# TRV1_0.net
KiCad netlist of a schematic drawn in Altium Designer
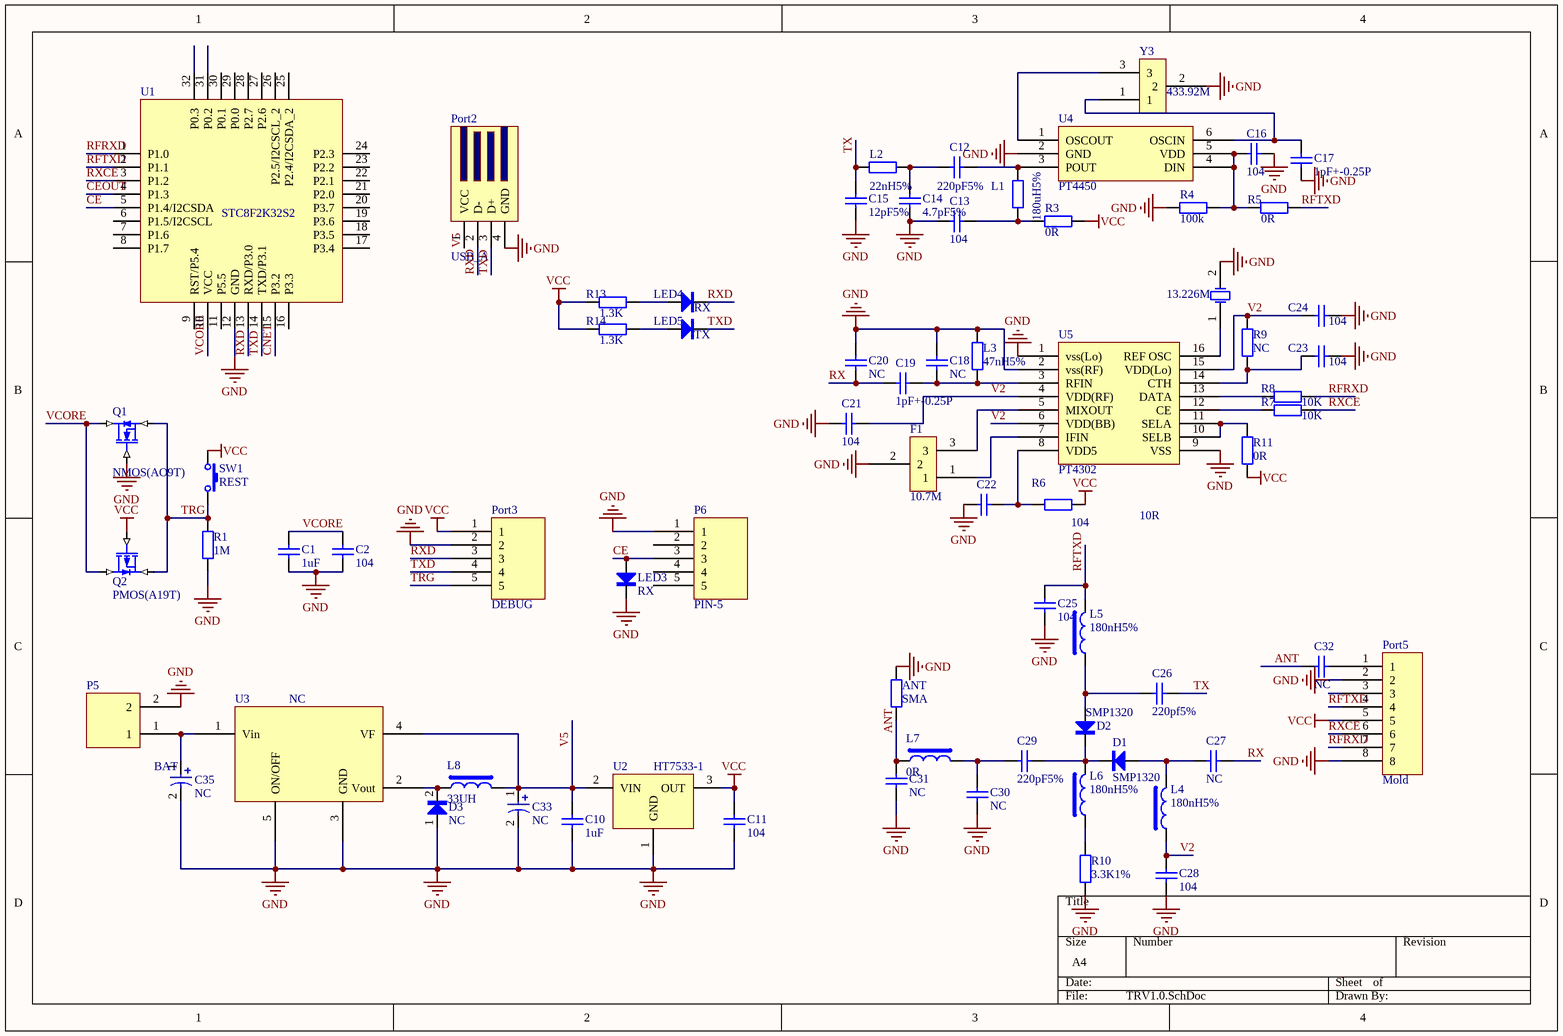
[diagram p0: TRV1.0.SchDoc]

(export (version "E")
  (design (tool "Eeschema 10.0.6"))
  (components
    (comp (ref "ANT")
      (value "SMA")
      (footprint "SWA-KE天线母座")
      (description "Resistor")
      (fields (field (name "PUBLISHER") "Altium Limited"))
      (libsource (lib "") (part "Res2_2"))
    )
    (comp (ref "C1")
      (value "1uF")
      (footprint "0603")
      (description "Capacitor")
      (fields (field (name "PUBLISHER") "Altium Limited"))
      (libsource (lib "Miscellaneous Devices") (part "Cap"))
    )
    (comp (ref "C2")
      (value "104")
      (footprint "0603")
      (description "Capacitor")
      (fields (field (name "PUBLISHER") "Altium Limited"))
      (libsource (lib "Miscellaneous Devices") (part "Cap"))
    )
    (comp (ref "C10")
      (value "1uF")
      (footprint "0603")
      (description "Capacitor")
      (fields (field (name "PUBLISHER") "Altium Limited"))
      (libsource (lib "Miscellaneous Devices") (part "Cap"))
    )
    (comp (ref "C11")
      (value "104")
      (footprint "0603")
      (description "Capacitor")
      (fields (field (name "PUBLISHER") "Altium Limited"))
      (libsource (lib "Miscellaneous Devices") (part "Cap"))
    )
    (comp (ref "C12")
      (value "220pF5%")
      (footprint "0603")
      (description "Capacitor")
      (fields (field (name "PUBLISHER") "Altium Limited"))
      (libsource (lib "Miscellaneous Devices") (part "Cap"))
    )
    (comp (ref "C13")
      (value "104")
      (footprint "0603")
      (description "Capacitor")
      (fields (field (name "PUBLISHER") "Altium Limited"))
      (libsource (lib "Miscellaneous Devices") (part "Cap"))
    )
    (comp (ref "C14")
      (value "4.7pF5%")
      (footprint "0603")
      (description "Capacitor")
      (fields (field (name "PUBLISHER") "Altium Limited"))
      (libsource (lib "Miscellaneous Devices") (part "Cap"))
    )
    (comp (ref "C15")
      (value "12pF5%")
      (footprint "0603")
      (description "Capacitor")
      (fields (field (name "PUBLISHER") "Altium Limited"))
      (libsource (lib "Miscellaneous Devices") (part "Cap"))
    )
    (comp (ref "C16")
      (value "104")
      (footprint "0603")
      (description "Capacitor")
      (fields (field (name "PUBLISHER") "Altium Limited"))
      (libsource (lib "Miscellaneous Devices") (part "Cap"))
    )
    (comp (ref "C17")
      (value "1pF+-0.25P")
      (footprint "0603")
      (description "Capacitor")
      (fields (field (name "PUBLISHER") "Altium Limited"))
      (libsource (lib "Miscellaneous Devices") (part "Cap"))
    )
    (comp (ref "C18")
      (value "NC")
      (footprint "0603")
      (description "Capacitor")
      (fields (field (name "PUBLISHER") "Altium Limited"))
      (libsource (lib "Miscellaneous Devices") (part "Cap"))
    )
    (comp (ref "C19")
      (value "1pF+-0.25P")
      (footprint "0603")
      (description "Capacitor")
      (fields (field (name "PUBLISHER") "Altium Limited"))
      (libsource (lib "Miscellaneous Devices") (part "Cap"))
    )
    (comp (ref "C20")
      (value "NC")
      (footprint "0603")
      (description "Capacitor")
      (fields (field (name "PUBLISHER") "Altium Limited"))
      (libsource (lib "Miscellaneous Devices") (part "Cap"))
    )
    (comp (ref "C21")
      (value "104")
      (footprint "0603")
      (description "Capacitor")
      (fields (field (name "PUBLISHER") "Altium Limited"))
      (libsource (lib "Miscellaneous Devices") (part "Cap"))
    )
    (comp (ref "C22")
      (value "104")
      (footprint "0603")
      (description "Capacitor")
      (fields (field (name "PUBLISHER") "Altium Limited"))
      (libsource (lib "Miscellaneous Devices") (part "Cap"))
    )
    (comp (ref "C23")
      (value "104")
      (footprint "0603")
      (description "Capacitor")
      (fields (field (name "PUBLISHER") "Altium Limited"))
      (libsource (lib "Miscellaneous Devices") (part "Cap"))
    )
    (comp (ref "C24")
      (value "104")
      (footprint "0603")
      (description "Capacitor")
      (fields (field (name "PUBLISHER") "Altium Limited"))
      (libsource (lib "Miscellaneous Devices") (part "Cap"))
    )
    (comp (ref "C25")
      (value "104")
      (footprint "0603")
      (description "Capacitor")
      (fields (field (name "PUBLISHER") "Altium Limited"))
      (libsource (lib "Miscellaneous Devices") (part "Cap"))
    )
    (comp (ref "C26")
      (value "220pf5%")
      (footprint "0603")
      (description "Capacitor")
      (fields (field (name "PUBLISHER") "Altium Limited"))
      (libsource (lib "Miscellaneous Devices") (part "Cap"))
    )
    (comp (ref "C27")
      (value "NC")
      (footprint "0603")
      (description "Capacitor")
      (fields (field (name "PUBLISHER") "Altium Limited"))
      (libsource (lib "Miscellaneous Devices") (part "Cap"))
    )
    (comp (ref "C28")
      (value "104")
      (footprint "0603")
      (description "Capacitor")
      (fields (field (name "PUBLISHER") "Altium Limited"))
      (libsource (lib "Miscellaneous Devices") (part "Cap"))
    )
    (comp (ref "C29")
      (value "220pF5%")
      (footprint "0603")
      (description "Capacitor")
      (fields (field (name "PUBLISHER") "Altium Limited"))
      (libsource (lib "Miscellaneous Devices") (part "Cap"))
    )
    (comp (ref "C30")
      (value "NC")
      (footprint "0603")
      (description "Capacitor")
      (fields (field (name "PUBLISHER") "Altium Limited"))
      (libsource (lib "Miscellaneous Devices") (part "Cap"))
    )
    (comp (ref "C31")
      (value "NC")
      (footprint "0603")
      (description "Capacitor")
      (fields (field (name "PUBLISHER") "Altium Limited"))
      (libsource (lib "Miscellaneous Devices") (part "Cap"))
    )
    (comp (ref "C32")
      (value "NC")
      (footprint "0603")
      (description "Capacitor")
      (fields (field (name "PUBLISHER") "Altium Limited"))
      (libsource (lib "Miscellaneous Devices") (part "Cap"))
    )
    (comp (ref "C33") (value "NC") (footprint "CAP6*12") (libsource (lib "dajiang SCH -DXP") (part "CAP2")))
    (comp (ref "C35") (value "NC") (footprint "CAP6*12") (libsource (lib "dajiang SCH -DXP") (part "CAP2")))
    (comp (ref "D1")
      (value "SMP1320")
      (footprint "0603")
      (description "diode")
      (libsource (lib "") (part "DIODE_2"))
    )
    (comp (ref "D2")
      (value "SMP1320")
      (footprint "0603")
      (description "diode")
      (libsource (lib "") (part "DIODE_1"))
    )
    (comp (ref "D3")
      (value "NC")
      (footprint "SS34")
      (description "diode")
      (libsource (lib "dajiang SCH -DXP") (part "DIODE"))
    )
    (comp (ref "F1") (value "10.7M") (footprint "PT4450 XTAL") (libsource (lib "MYSHC") (part "Filter")))
    (comp (ref "L1")
      (value "180uH5%")
      (footprint "0603")
      (description "Resistor")
      (fields (field (name "PUBLISHER") "Altium Limited"))
      (libsource (lib "") (part "Res2_1"))
    )
    (comp (ref "L2")
      (value "22nH5%")
      (footprint "0603")
      (description "Resistor")
      (fields (field (name "PUBLISHER") "Altium Limited"))
      (libsource (lib "") (part "Res2_3"))
    )
    (comp (ref "L3")
      (value "47nH5%")
      (footprint "0603")
      (description "Resistor")
      (fields (field (name "PUBLISHER") "Altium Limited"))
      (libsource (lib "") (part "Res2_2"))
    )
    (comp (ref "L4")
      (value "180nH5%")
      (footprint "0603")
      (description "Inductor")
      (libsource (lib "dajiang SCH -DXP") (part "L"))
    )
    (comp (ref "L5")
      (value "180nH5%")
      (footprint "0603")
      (description "Inductor")
      (libsource (lib "dajiang SCH -DXP") (part "L"))
    )
    (comp (ref "L6")
      (value "180nH5%")
      (footprint "0603")
      (description "Inductor")
      (libsource (lib "dajiang SCH -DXP") (part "L"))
    )
    (comp (ref "L7")
      (value "0R")
      (footprint "0603")
      (description "Inductor")
      (libsource (lib "") (part "L_1"))
    )
    (comp (ref "L8")
      (value "33UH")
      (footprint "CD75")
      (description "Inductor")
      (libsource (lib "") (part "L_1"))
    )
    (comp (ref "LED3")
      (value "RX")
      (footprint "LED-0603")
      (description "diode")
      (libsource (lib "") (part "DIODE_1"))
    )
    (comp (ref "LED4")
      (value "RX")
      (footprint "LED-0603")
      (description "diode")
      (libsource (lib "") (part "DIODE_3"))
    )
    (comp (ref "LED5")
      (value "TX")
      (footprint "LED-0603")
      (description "diode")
      (libsource (lib "") (part "DIODE_3"))
    )
    (comp (ref "P5") (value "BAT") (footprint "DIP2-2.54") (libsource (lib "MYSHC") (part "BAT")))
    (comp (ref "P6") (value "PIN-5") (footprint "PCBComponent_1") (libsource (lib "MYSHC") (part "PIN-5")))
    (comp (ref "Port2") (value "USB_A") (footprint "USB-A") (libsource (lib "mylib") (part "USB")))
    (comp (ref "Port3") (value "DEBUG") (footprint "STC_DEBUG") (libsource (lib "MYSHC") (part "PIN-5")))
    (comp (ref "Port5") (value "Mold") (footprint "Pin-8") (libsource (lib "MYSHC") (part "Pin-8")))
    (comp (ref "Q1")
      (value "NMOS(AO9T)")
      (footprint "SOT-23")
      (description "mosfet")
      (libsource (lib "dajiang SCH -DXP") (part "MOSFET-N"))
    )
    (comp (ref "Q2")
      (value "PMOS(A19T)")
      (footprint "SOT-23")
      (description "mosfet")
      (libsource (lib "dajiang SCH -DXP") (part "MOSFET-P"))
    )
    (comp (ref "R1")
      (value "1M")
      (footprint "0603")
      (description "Resistor")
      (fields (field (name "PUBLISHER") "Altium Limited"))
      (libsource (lib "") (part "Res2_2"))
    )
    (comp (ref "R3")
      (value "0R")
      (footprint "0603")
      (description "Resistor")
      (fields (field (name "PUBLISHER") "Altium Limited"))
      (libsource (lib "Miscellaneous Devices") (part "Res2"))
    )
    (comp (ref "R4")
      (value "100k")
      (footprint "0603")
      (description "Resistor")
      (fields (field (name "PUBLISHER") "Altium Limited"))
      (libsource (lib "Miscellaneous Devices") (part "Res2"))
    )
    (comp (ref "R5")
      (value "0R")
      (footprint "0603")
      (description "Resistor")
      (fields (field (name "PUBLISHER") "Altium Limited"))
      (libsource (lib "Miscellaneous Devices") (part "Res2"))
    )
    (comp (ref "R6")
      (value "10R")
      (footprint "0603")
      (description "Resistor")
      (fields (field (name "PUBLISHER") "Altium Limited"))
      (libsource (lib "Miscellaneous Devices") (part "Res2"))
    )
    (comp (ref "R7")
      (value "10K")
      (footprint "0603")
      (description "Resistor")
      (fields (field (name "PUBLISHER") "Altium Limited"))
      (libsource (lib "Miscellaneous Devices") (part "Res2"))
    )
    (comp (ref "R8")
      (value "10K")
      (footprint "0603")
      (description "Resistor")
      (fields (field (name "PUBLISHER") "Altium Limited"))
      (libsource (lib "Miscellaneous Devices") (part "Res2"))
    )
    (comp (ref "R9")
      (value "NC")
      (footprint "0603")
      (description "Resistor")
      (fields (field (name "PUBLISHER") "Altium Limited"))
      (libsource (lib "") (part "Res2_1"))
    )
    (comp (ref "R10")
      (value "3.3K1%")
      (footprint "0603")
      (description "Resistor")
      (fields (field (name "PUBLISHER") "Altium Limited"))
      (libsource (lib "") (part "Res2_1"))
    )
    (comp (ref "R11")
      (value "0R")
      (footprint "0603")
      (description "Resistor")
      (fields (field (name "PUBLISHER") "Altium Limited"))
      (libsource (lib "") (part "Res2_1"))
    )
    (comp (ref "R13")
      (value "1.3K")
      (footprint "0603")
      (description "Resistor")
      (fields (field (name "PUBLISHER") "Altium Limited"))
      (libsource (lib "Miscellaneous Devices") (part "Res2"))
    )
    (comp (ref "R14")
      (value "1.3K")
      (footprint "0603")
      (description "Resistor")
      (fields (field (name "PUBLISHER") "Altium Limited"))
      (libsource (lib "Miscellaneous Devices") (part "Res2"))
    )
    (comp (ref "SW1")
      (value "REST")
      (footprint "SW-1")
      (description "key")
      (libsource (lib "dajiang SCH -DXP") (part "SW-P"))
    )
    (comp (ref "U1")
      (value "STC8F2K32S2")
      (footprint "LQPF-32")
      (libsource (lib "mylib") (part "STC8F2K64S2"))
    )
    (comp (ref "U2") (value "HT7533-1") (footprint "3A5A3D") (libsource (lib "mylib") (part "HT7533-1")))
    (comp (ref "U3") (value "NC") (footprint "TS5B_N") (libsource (lib "MYSHC") (part "LM2596")))
    (comp (ref "U4") (value "PT4450") (libsource (lib "MYSHC") (part "PT4450")))
    (comp (ref "U5") (value "PT4302") (footprint "PT4302") (libsource (lib "MYSHC") (part "PT4302")))
    (comp (ref "Y3")
      (value "433.92M")
      (footprint "PT4450 XTAL")
      (libsource (lib "MYSHC") (part "PT4450-XTAL"))
    )
    (comp (ref "Y4")
      (value "13.226M")
      (footprint "PT4306 XTAL")
      (description "Crystal Oscillator")
      (libsource (lib "DT-852A(3)") (part "XTAL"))
    )
  )
  (nets
    (net (code "1") (name "/ANT") (class "Default")
      (node (ref "ANT") (pin "1") (pinfunction "1_1") (pintype "passive"))
      (node (ref "C31") (pin "1") (pinfunction "1_1") (pintype "passive"))
      (node (ref "C32") (pin "1") (pinfunction "1_1") (pintype "passive"))
      (node (ref "L7") (pin "1") (pinfunction "1_1") (pintype "passive"))
    )
    (net (code "2") (name "/CE") (class "Default")
      (node (ref "LED3") (pin "1") (pinfunction "1_1") (pintype "passive"))
      (node (ref "P6") (pin "3") (pinfunction "3_3") (pintype "passive"))
      (node (ref "U1") (pin "5") (pinfunction "P1.4/I2CSDA_5") (pintype "passive"))
    )
    (net (code "3") (name "/CEOUT") (class "Default")
      (node (ref "U1") (pin "4") (pinfunction "P1.3_4") (pintype "passive"))
    )
    (net (code "4") (name "/CNET") (class "Default")
      (node (ref "U1") (pin "15") (pinfunction "P3.2_15") (pintype "passive"))
    )
    (net (code "5") (name "/RFRXD") (class "Default")
      (node (ref "Port5") (pin "7") (pinfunction "7_7") (pintype "passive"))
      (node (ref "R8") (pin "1") (pinfunction "1_1") (pintype "passive"))
      (node (ref "U1") (pin "1") (pinfunction "P1.0_1") (pintype "passive"))
    )
    (net (code "6") (name "/RFTXD") (class "Default")
      (node (ref "C25") (pin "1") (pinfunction "1_1") (pintype "passive"))
      (node (ref "L5") (pin "2") (pinfunction "2_2") (pintype "passive"))
      (node (ref "Port5") (pin "4") (pinfunction "4_4") (pintype "passive"))
      (node (ref "R5") (pin "1") (pinfunction "1_1") (pintype "passive"))
      (node (ref "U1") (pin "2") (pinfunction "P1.1_2") (pintype "passive"))
    )
    (net (code "7") (name "/RX") (class "Default")
      (node (ref "C19") (pin "1") (pinfunction "1_1") (pintype "passive"))
      (node (ref "C20") (pin "1") (pinfunction "1_1") (pintype "passive"))
      (node (ref "C27") (pin "2") (pinfunction "2_2") (pintype "passive"))
    )
    (net (code "8") (name "/RXCE") (class "Default")
      (node (ref "Port5") (pin "6") (pinfunction "6_6") (pintype "passive"))
      (node (ref "R7") (pin "1") (pinfunction "1_1") (pintype "passive"))
      (node (ref "U1") (pin "3") (pinfunction "P1.2_3") (pintype "passive"))
    )
    (net (code "9") (name "/RXD") (class "Default")
      (node (ref "LED4") (pin "2") (pinfunction "2_2") (pintype "passive"))
      (node (ref "Port2") (pin "2") (pinfunction "D-_2") (pintype "passive"))
      (node (ref "Port3") (pin "3") (pinfunction "3_3") (pintype "passive"))
      (node (ref "U1") (pin "13") (pinfunction "RXD/P3.0_13") (pintype "passive"))
    )
    (net (code "10") (name "/TRG") (class "Default")
      (node (ref "Port3") (pin "5") (pinfunction "5_5") (pintype "passive"))
      (node (ref "Q1") (pin "2") (pinfunction "D_2") (pintype "input"))
      (node (ref "Q2") (pin "2") (pinfunction "S_2") (pintype "input"))
      (node (ref "R1") (pin "2") (pinfunction "2_2") (pintype "passive"))
      (node (ref "SW1") (pin "2") (pinfunction "2_2") (pintype "passive"))
    )
    (net (code "11") (name "/TX") (class "Default")
      (node (ref "C15") (pin "2") (pinfunction "2_2") (pintype "passive"))
      (node (ref "C26") (pin "2") (pinfunction "2_2") (pintype "passive"))
      (node (ref "L2") (pin "1") (pinfunction "1_1") (pintype "passive"))
    )
    (net (code "12") (name "/TXD") (class "Default")
      (node (ref "LED5") (pin "2") (pinfunction "2_2") (pintype "passive"))
      (node (ref "Port2") (pin "3") (pinfunction "D+_3") (pintype "passive"))
      (node (ref "Port3") (pin "4") (pinfunction "4_4") (pintype "passive"))
      (node (ref "U1") (pin "14") (pinfunction "TXD/P3.1_14") (pintype "passive"))
    )
    (net (code "13") (name "/V2") (class "Default")
      (node (ref "C21") (pin "1") (pinfunction "1_1") (pintype "passive"))
      (node (ref "C24") (pin "2") (pinfunction "2_2") (pintype "passive"))
      (node (ref "C28") (pin "2") (pinfunction "2_2") (pintype "passive"))
      (node (ref "L4") (pin "1") (pinfunction "1_1") (pintype "passive"))
      (node (ref "R9") (pin "1") (pinfunction "1_1") (pintype "passive"))
      (node (ref "U5") (pin "15") (pinfunction "VDD(Lo)_15") (pintype "passive"))
      (node (ref "U5") (pin "4") (pinfunction "VDD(RF)_4") (pintype "passive"))
      (node (ref "U5") (pin "6") (pinfunction "VDD(BB)_6") (pintype "passive"))
    )
    (net (code "14") (name "/V5") (class "Default")
      (node (ref "C10") (pin "1") (pinfunction "1_1") (pintype "passive"))
      (node (ref "C33") (pin "1") (pinfunction "1_1") (pintype "passive"))
      (node (ref "L8") (pin "2") (pinfunction "2_2") (pintype "passive"))
      (node (ref "Port2") (pin "1") (pinfunction "VCC_1") (pintype "passive"))
      (node (ref "U2") (pin "2") (pinfunction "VIN_2") (pintype "passive"))
      (node (ref "U3") (pin "4") (pinfunction "VF_4") (pintype "passive"))
    )
    (net (code "15") (name "/VCORE") (class "Default")
      (node (ref "C1") (pin "2") (pinfunction "2_2") (pintype "passive"))
      (node (ref "C2") (pin "2") (pinfunction "2_2") (pintype "passive"))
      (node (ref "Q1") (pin "3") (pinfunction "S_3") (pintype "input"))
      (node (ref "Q2") (pin "3") (pinfunction "D_3") (pintype "input"))
      (node (ref "U1") (pin "10") (pinfunction "VCC_10") (pintype "passive"))
    )
    (net (code "16") (name "GND") (class "Default")
      (node (ref "ANT") (pin "2") (pinfunction "2_2") (pintype "passive"))
      (node (ref "C1") (pin "1") (pinfunction "1_1") (pintype "passive"))
      (node (ref "C10") (pin "2") (pinfunction "2_2") (pintype "passive"))
      (node (ref "C11") (pin "2") (pinfunction "2_2") (pintype "passive"))
      (node (ref "C13") (pin "1") (pinfunction "1_1") (pintype "passive"))
      (node (ref "C14") (pin "1") (pinfunction "1_1") (pintype "passive"))
      (node (ref "C15") (pin "1") (pinfunction "1_1") (pintype "passive"))
      (node (ref "C16") (pin "1") (pinfunction "1_1") (pintype "passive"))
      (node (ref "C17") (pin "2") (pinfunction "2_2") (pintype "passive"))
      (node (ref "C18") (pin "1") (pinfunction "1_1") (pintype "passive"))
      (node (ref "C2") (pin "1") (pinfunction "1_1") (pintype "passive"))
      (node (ref "C20") (pin "2") (pinfunction "2_2") (pintype "passive"))
      (node (ref "C21") (pin "2") (pinfunction "2_2") (pintype "passive"))
      (node (ref "C22") (pin "2") (pinfunction "2_2") (pintype "passive"))
      (node (ref "C23") (pin "1") (pinfunction "1_1") (pintype "passive"))
      (node (ref "C24") (pin "1") (pinfunction "1_1") (pintype "passive"))
      (node (ref "C25") (pin "2") (pinfunction "2_2") (pintype "passive"))
      (node (ref "C28") (pin "1") (pinfunction "1_1") (pintype "passive"))
      (node (ref "C30") (pin "2") (pinfunction "2_2") (pintype "passive"))
      (node (ref "C31") (pin "2") (pinfunction "2_2") (pintype "passive"))
      (node (ref "C33") (pin "2") (pinfunction "2_2") (pintype "passive"))
      (node (ref "C35") (pin "2") (pinfunction "2_2") (pintype "passive"))
      (node (ref "D3") (pin "1") (pinfunction "1_1") (pintype "passive"))
      (node (ref "F1") (pin "2") (pinfunction "2_2") (pintype "passive"))
      (node (ref "L3") (pin "2") (pinfunction "2_2") (pintype "passive"))
      (node (ref "LED3") (pin "2") (pinfunction "2_2") (pintype "passive"))
      (node (ref "P5") (pin "2") (pinfunction "2_2") (pintype "passive"))
      (node (ref "P6") (pin "1") (pinfunction "1_1") (pintype "passive"))
      (node (ref "Port2") (pin "4") (pinfunction "GND_4") (pintype "passive"))
      (node (ref "Port3") (pin "2") (pinfunction "2_2") (pintype "passive"))
      (node (ref "Port5") (pin "2") (pinfunction "2_2") (pintype "passive"))
      (node (ref "Port5") (pin "8") (pinfunction "8_8") (pintype "passive"))
      (node (ref "Q1") (pin "1") (pinfunction "G_1") (pintype "input"))
      (node (ref "R1") (pin "1") (pinfunction "1_1") (pintype "passive"))
      (node (ref "R10") (pin "2") (pinfunction "2_2") (pintype "passive"))
      (node (ref "R4") (pin "2") (pinfunction "2_2") (pintype "passive"))
      (node (ref "U1") (pin "12") (pinfunction "GND_12") (pintype "passive"))
      (node (ref "U2") (pin "1") (pinfunction "GND_1") (pintype "passive"))
      (node (ref "U3") (pin "3") (pinfunction "GND_3") (pintype "passive"))
      (node (ref "U3") (pin "5") (pinfunction "ON/OFF_5") (pintype "passive"))
      (node (ref "U4") (pin "2") (pinfunction "GND_2") (pintype "passive"))
      (node (ref "U5") (pin "1") (pinfunction "vss(Lo)_1") (pintype "passive"))
      (node (ref "U5") (pin "2") (pinfunction "vss(RF)_2") (pintype "passive"))
      (node (ref "U5") (pin "9") (pinfunction "VSS_9") (pintype "passive"))
      (node (ref "Y3") (pin "2") (pinfunction "2_2") (pintype "passive"))
      (node (ref "Y4") (pin "2") (pinfunction "OSC2_2") (pintype "passive"))
    )
    (net (code "17") (name "Net-(C12-Pad1)") (class "Default")
      (node (ref "C12") (pin "1") (pinfunction "1_1") (pintype "passive"))
      (node (ref "C14") (pin "2") (pinfunction "2_2") (pintype "passive"))
      (node (ref "L2") (pin "2") (pinfunction "2_2") (pintype "passive"))
    )
    (net (code "18") (name "Net-(C13-Pad2)") (class "Default")
      (node (ref "C13") (pin "2") (pinfunction "2_2") (pintype "passive"))
      (node (ref "L1") (pin "2") (pinfunction "2_2") (pintype "passive"))
      (node (ref "R3") (pin "2") (pinfunction "2_2") (pintype "passive"))
    )
    (net (code "19") (name "Net-(C26-Pad1)") (class "Default")
      (node (ref "C26") (pin "1") (pinfunction "1_1") (pintype "passive"))
      (node (ref "D2") (pin "1") (pinfunction "1_1") (pintype "passive"))
      (node (ref "L5") (pin "1") (pinfunction "1_1") (pintype "passive"))
    )
    (net (code "20") (name "Net-(C27-Pad1)") (class "Default")
      (node (ref "C27") (pin "1") (pinfunction "1_1") (pintype "passive"))
      (node (ref "D1") (pin "1") (pinfunction "1_1") (pintype "passive"))
      (node (ref "L4") (pin "2") (pinfunction "2_2") (pintype "passive"))
    )
    (net (code "21") (name "Net-(C29-Pad1)") (class "Default")
      (node (ref "C29") (pin "1") (pinfunction "1_1") (pintype "passive"))
      (node (ref "D1") (pin "2") (pinfunction "2_2") (pintype "passive"))
      (node (ref "D2") (pin "2") (pinfunction "2_2") (pintype "passive"))
      (node (ref "L6") (pin "2") (pinfunction "2_2") (pintype "passive"))
    )
    (net (code "22") (name "Net-(C29-Pad2)") (class "Default")
      (node (ref "C29") (pin "2") (pinfunction "2_2") (pintype "passive"))
      (node (ref "C30") (pin "1") (pinfunction "1_1") (pintype "passive"))
      (node (ref "L7") (pin "2") (pinfunction "2_2") (pintype "passive"))
    )
    (net (code "23") (name "Net-(C32-Pad2)") (class "Default")
      (node (ref "C32") (pin "2") (pinfunction "2_2") (pintype "passive"))
      (node (ref "Port5") (pin "1") (pinfunction "1_1") (pintype "passive"))
    )
    (net (code "24") (name "Net-(L6-Pad1)") (class "Default")
      (node (ref "L6") (pin "1") (pinfunction "1_1") (pintype "passive"))
      (node (ref "R10") (pin "1") (pinfunction "1_1") (pintype "passive"))
    )
    (net (code "25") (name "Net-(LED4-Pad1)") (class "Default")
      (node (ref "LED4") (pin "1") (pinfunction "1_1") (pintype "passive"))
      (node (ref "R13") (pin "1") (pinfunction "1_1") (pintype "passive"))
    )
    (net (code "26") (name "Net-(LED5-Pad1)") (class "Default")
      (node (ref "LED5") (pin "1") (pinfunction "1_1") (pintype "passive"))
      (node (ref "R14") (pin "1") (pinfunction "1_1") (pintype "passive"))
    )
    (net (code "27") (name "Net-(U3-Vin)") (class "Default")
      (node (ref "C35") (pin "1") (pinfunction "1_1") (pintype "passive"))
      (node (ref "P5") (pin "1") (pinfunction "1_1") (pintype "passive"))
      (node (ref "U3") (pin "1") (pinfunction "Vin_1") (pintype "passive"))
    )
    (net (code "28") (name "Net-(U3-Vout)") (class "Default")
      (node (ref "D3") (pin "2") (pinfunction "2_2") (pintype "passive"))
      (node (ref "L8") (pin "1") (pinfunction "1_1") (pintype "passive"))
      (node (ref "U3") (pin "2") (pinfunction "Vout_2") (pintype "passive"))
    )
    (net (code "29") (name "Net-(U4-DIN)") (class "Default")
      (node (ref "C16") (pin "2") (pinfunction "2_2") (pintype "passive"))
      (node (ref "R4") (pin "1") (pinfunction "1_1") (pintype "passive"))
      (node (ref "R5") (pin "2") (pinfunction "2_2") (pintype "passive"))
      (node (ref "U4") (pin "4") (pinfunction "DIN_4") (pintype "passive"))
      (node (ref "U4") (pin "5") (pinfunction "VDD_5") (pintype "passive"))
    )
    (net (code "30") (name "Net-(U4-OSCIN)") (class "Default")
      (node (ref "C17") (pin "1") (pinfunction "1_1") (pintype "passive"))
      (node (ref "U4") (pin "6") (pinfunction "OSCIN_6") (pintype "passive"))
      (node (ref "Y3") (pin "1") (pinfunction "1_1") (pintype "passive"))
    )
    (net (code "31") (name "Net-(U4-OSCOUT)") (class "Default")
      (node (ref "U4") (pin "1") (pinfunction "OSCOUT_1") (pintype "passive"))
      (node (ref "Y3") (pin "3") (pinfunction "3_3") (pintype "passive"))
    )
    (net (code "32") (name "Net-(U4-POUT)") (class "Default")
      (node (ref "C12") (pin "2") (pinfunction "2_2") (pintype "passive"))
      (node (ref "L1") (pin "1") (pinfunction "1_1") (pintype "passive"))
      (node (ref "U4") (pin "3") (pinfunction "POUT_3") (pintype "passive"))
    )
    (net (code "33") (name "Net-(U5-CE)") (class "Default")
      (node (ref "R7") (pin "2") (pinfunction "2_2") (pintype "passive"))
      (node (ref "U5") (pin "12") (pinfunction "CE_12") (pintype "passive"))
    )
    (net (code "34") (name "Net-(U5-CTH)") (class "Default")
      (node (ref "C23") (pin "2") (pinfunction "2_2") (pintype "passive"))
      (node (ref "R9") (pin "2") (pinfunction "2_2") (pintype "passive"))
      (node (ref "U5") (pin "14") (pinfunction "CTH_14") (pintype "passive"))
    )
    (net (code "35") (name "Net-(U5-DATA)") (class "Default")
      (node (ref "R8") (pin "2") (pinfunction "2_2") (pintype "passive"))
      (node (ref "U5") (pin "13") (pinfunction "DATA_13") (pintype "passive"))
    )
    (net (code "36") (name "Net-(U5-IFIN)") (class "Default")
      (node (ref "F1") (pin "1") (pinfunction "1_1") (pintype "passive"))
      (node (ref "U5") (pin "7") (pinfunction "IFIN_7") (pintype "passive"))
    )
    (net (code "37") (name "Net-(U5-MIXOUT)") (class "Default")
      (node (ref "F1") (pin "3") (pinfunction "3_3") (pintype "passive"))
      (node (ref "U5") (pin "5") (pinfunction "MIXOUT_5") (pintype "passive"))
    )
    (net (code "38") (name "Net-(U5-REF_OSC)") (class "Default")
      (node (ref "U5") (pin "16") (pinfunction "REF_OSC_16") (pintype "passive"))
      (node (ref "Y4") (pin "1") (pinfunction "OSC1_1") (pintype "passive"))
    )
    (net (code "39") (name "Net-(U5-RFIN)") (class "Default")
      (node (ref "C18") (pin "2") (pinfunction "2_2") (pintype "passive"))
      (node (ref "C19") (pin "2") (pinfunction "2_2") (pintype "passive"))
      (node (ref "L3") (pin "1") (pinfunction "1_1") (pintype "passive"))
      (node (ref "U5") (pin "3") (pinfunction "RFIN_3") (pintype "passive"))
    )
    (net (code "40") (name "Net-(U5-SELA)") (class "Default")
      (node (ref "R11") (pin "1") (pinfunction "1_1") (pintype "passive"))
      (node (ref "U5") (pin "10") (pinfunction "SELB_10") (pintype "passive"))
      (node (ref "U5") (pin "11") (pinfunction "SELA_11") (pintype "passive"))
    )
    (net (code "41") (name "Net-(U5-VDD5)") (class "Default")
      (node (ref "C22") (pin "1") (pinfunction "1_1") (pintype "passive"))
      (node (ref "R6") (pin "2") (pinfunction "2_2") (pintype "passive"))
      (node (ref "U5") (pin "8") (pinfunction "VDD5_8") (pintype "passive"))
    )
    (net (code "42") (name "VCC") (class "Default")
      (node (ref "C11") (pin "1") (pinfunction "1_1") (pintype "passive"))
      (node (ref "Port3") (pin "1") (pinfunction "1_1") (pintype "passive"))
      (node (ref "Port5") (pin "5") (pinfunction "5_5") (pintype "passive"))
      (node (ref "Q2") (pin "1") (pinfunction "G_1") (pintype "input"))
      (node (ref "R11") (pin "2") (pinfunction "2_2") (pintype "passive"))
      (node (ref "R13") (pin "2") (pinfunction "2_2") (pintype "passive"))
      (node (ref "R14") (pin "2") (pinfunction "2_2") (pintype "passive"))
      (node (ref "R3") (pin "1") (pinfunction "1_1") (pintype "passive"))
      (node (ref "R6") (pin "1") (pinfunction "1_1") (pintype "passive"))
      (node (ref "SW1") (pin "1") (pinfunction "1_1") (pintype "passive"))
      (node (ref "U2") (pin "3") (pinfunction "OUT_3") (pintype "passive"))
    )
    (net (code "43") (name "unconnected-(P6-Pad2)") (class "Default")
      (node (ref "P6") (pin "2") (pinfunction "2_2") (pintype "passive"))
    )
    (net (code "44") (name "unconnected-(P6-Pad4)") (class "Default")
      (node (ref "P6") (pin "4") (pinfunction "4_4") (pintype "passive"))
    )
    (net (code "45") (name "unconnected-(P6-Pad5)") (class "Default")
      (node (ref "P6") (pin "5") (pinfunction "5_5") (pintype "passive"))
    )
    (net (code "46") (name "unconnected-(Port5-Pad3)") (class "Default")
      (node (ref "Port5") (pin "3") (pinfunction "3_3") (pintype "passive"))
    )
    (net (code "47") (name "unconnected-(U1-P0.0-Pad29)") (class "Default")
      (node (ref "U1") (pin "29") (pinfunction "P0.0_29") (pintype "passive"))
    )
    (net (code "48") (name "unconnected-(U1-P0.1-Pad30)") (class "Default")
      (node (ref "U1") (pin "30") (pinfunction "P0.1_30") (pintype "passive"))
    )
    (net (code "49") (name "unconnected-(U1-P0.2-Pad31)") (class "Default")
      (node (ref "U1") (pin "31") (pinfunction "P0.2_31") (pintype "passive"))
    )
    (net (code "50") (name "unconnected-(U1-P0.3-Pad32)") (class "Default")
      (node (ref "U1") (pin "32") (pinfunction "P0.3_32") (pintype "passive"))
    )
    (net (code "51") (name "unconnected-(U1-P1.5{slash}I2CSCL-Pad6)") (class "Default")
      (node (ref "U1") (pin "6") (pinfunction "P1.5/I2CSCL_6") (pintype "passive"))
    )
    (net (code "52") (name "unconnected-(U1-P1.6-Pad7)") (class "Default")
      (node (ref "U1") (pin "7") (pinfunction "P1.6_7") (pintype "passive"))
    )
    (net (code "53") (name "unconnected-(U1-P1.7-Pad8)") (class "Default")
      (node (ref "U1") (pin "8") (pinfunction "P1.7_8") (pintype "passive"))
    )
    (net (code "54") (name "unconnected-(U1-P2.0-Pad21)") (class "Default")
      (node (ref "U1") (pin "21") (pinfunction "P2.0_21") (pintype "passive"))
    )
    (net (code "55") (name "unconnected-(U1-P2.1-Pad22)") (class "Default")
      (node (ref "U1") (pin "22") (pinfunction "P2.1_22") (pintype "passive"))
    )
    (net (code "56") (name "unconnected-(U1-P2.2-Pad23)") (class "Default")
      (node (ref "U1") (pin "23") (pinfunction "P2.2_23") (pintype "passive"))
    )
    (net (code "57") (name "unconnected-(U1-P2.3-Pad24)") (class "Default")
      (node (ref "U1") (pin "24") (pinfunction "P2.3_24") (pintype "passive"))
    )
    (net (code "58") (name "unconnected-(U1-P2.4{slash}I2CSDA_2-Pad25)") (class "Default")
      (node (ref "U1") (pin "25") (pinfunction "P2.4/I2CSDA_2_25") (pintype "passive"))
    )
    (net (code "59") (name "unconnected-(U1-P2.5{slash}I2CSCL_2-Pad26)") (class "Default")
      (node (ref "U1") (pin "26") (pinfunction "P2.5/I2CSCL_2_26") (pintype "passive"))
    )
    (net (code "60") (name "unconnected-(U1-P2.6-Pad27)") (class "Default")
      (node (ref "U1") (pin "27") (pinfunction "P2.6_27") (pintype "passive"))
    )
    (net (code "61") (name "unconnected-(U1-P2.7-Pad28)") (class "Default")
      (node (ref "U1") (pin "28") (pinfunction "P2.7_28") (pintype "passive"))
    )
    (net (code "62") (name "unconnected-(U1-P3.3-Pad16)") (class "Default")
      (node (ref "U1") (pin "16") (pinfunction "P3.3_16") (pintype "passive"))
    )
    (net (code "63") (name "unconnected-(U1-P3.4-Pad17)") (class "Default")
      (node (ref "U1") (pin "17") (pinfunction "P3.4_17") (pintype "passive"))
    )
    (net (code "64") (name "unconnected-(U1-P3.5-Pad18)") (class "Default")
      (node (ref "U1") (pin "18") (pinfunction "P3.5_18") (pintype "passive"))
    )
    (net (code "65") (name "unconnected-(U1-P3.6-Pad19)") (class "Default")
      (node (ref "U1") (pin "19") (pinfunction "P3.6_19") (pintype "passive"))
    )
    (net (code "66") (name "unconnected-(U1-P3.7-Pad20)") (class "Default")
      (node (ref "U1") (pin "20") (pinfunction "P3.7_20") (pintype "passive"))
    )
    (net (code "67") (name "unconnected-(U1-P5.5-Pad11)") (class "Default")
      (node (ref "U1") (pin "11") (pinfunction "P5.5_11") (pintype "passive"))
    )
    (net (code "68") (name "unconnected-(U1-RST{slash}P5.4-Pad9)") (class "Default")
      (node (ref "U1") (pin "9") (pinfunction "RST/P5.4_9") (pintype "passive"))
    )
  )
)
